# POWER.net
KiCad netlist of a schematic drawn in Altium Designer
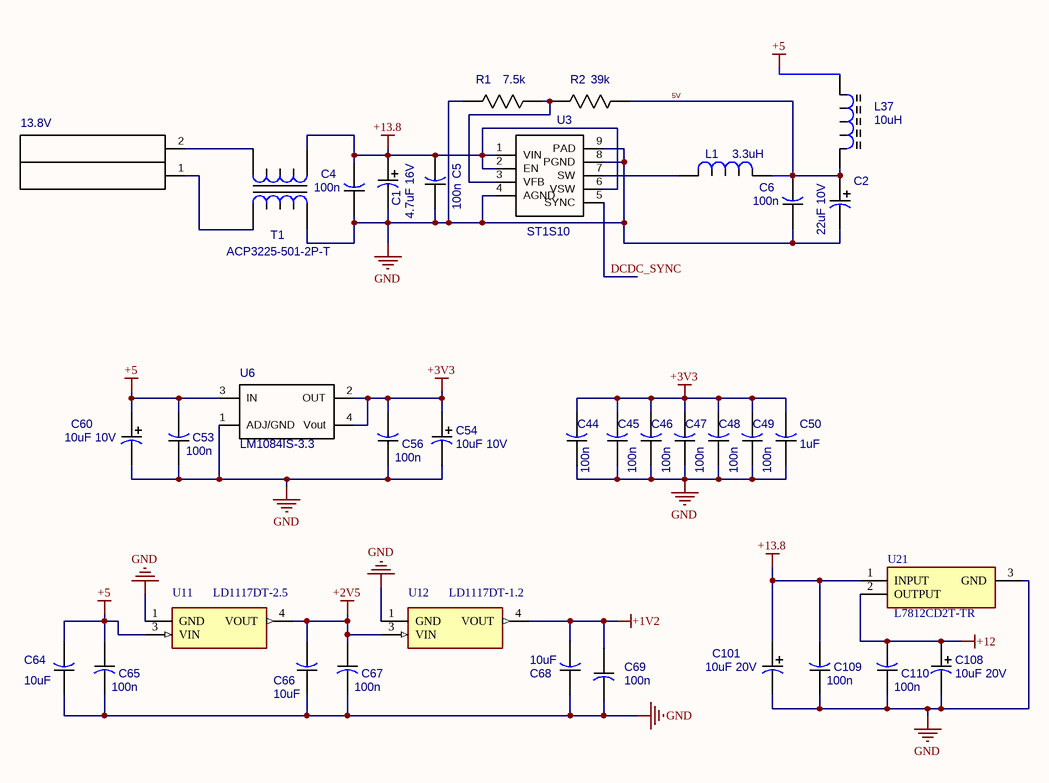
[diagram p0: POWER.SchDoc]

(export (version "E")
  (design (tool "Eeschema 10.0.6"))
  (components
    (comp (ref "13.8V") (value "JX2") (footprint "JX2") (libsource (lib "*") (part "JX2")))
    (comp (ref "C1")
      (value "4.7uF 16V")
      (footprint "CAPAE_6.6x6.6h5.4")
      (description "CAPAE_6.6x6.6h5.4")
      (libsource (lib "*") (part "CAPAE_6.6x6.6h5.4"))
    )
    (comp (ref "C2")
      (value "22uF 10V")
      (footprint "CAPAE_4.3x4.3h5.4")
      (description "CAPAE_4.3x4.3h5.4")
      (libsource (lib "*") (part "CAPAE_4.3x4.3h5.4"))
    )
    (comp (ref "C4")
      (value "100n")
      (footprint "CAP_0805")
      (description "CAP_0805")
      (libsource (lib "*") (part "CAP_0805"))
    )
    (comp (ref "C5")
      (value "100n")
      (footprint "CAP_0805")
      (description "CAP_0805")
      (libsource (lib "*") (part "CAP_0805"))
    )
    (comp (ref "C6")
      (value "100n")
      (footprint "CAP_0805")
      (description "CAP_0805")
      (libsource (lib "*") (part "CAP_0805"))
    )
    (comp (ref "C44")
      (value "100n")
      (footprint "CAP_0805")
      (description "CAP_0805")
      (libsource (lib "*") (part "CAP_0805"))
    )
    (comp (ref "C45")
      (value "100n")
      (footprint "CAP_0805")
      (description "CAP_0805")
      (libsource (lib "*") (part "CAP_0805"))
    )
    (comp (ref "C46")
      (value "100n")
      (footprint "CAP_0805")
      (description "CAP_0805")
      (libsource (lib "*") (part "CAP_0805"))
    )
    (comp (ref "C47")
      (value "100n")
      (footprint "CAP_0805")
      (description "CAP_0805")
      (libsource (lib "*") (part "CAP_0805"))
    )
    (comp (ref "C48")
      (value "100n")
      (footprint "CAP_0805")
      (description "CAP_0805")
      (libsource (lib "*") (part "CAP_0805"))
    )
    (comp (ref "C49")
      (value "100n")
      (footprint "CAP_0805")
      (description "CAP_0805")
      (libsource (lib "*") (part "CAP_0805"))
    )
    (comp (ref "C50")
      (value "1uF")
      (footprint "CAP_0805")
      (description "CAP_0805")
      (fields (field (name "Comment") "10uF"))
      (libsource (lib "*") (part "CAP_0805"))
    )
    (comp (ref "C53")
      (value "100n")
      (footprint "CAP_0805")
      (description "CAP_0805")
      (libsource (lib "*") (part "CAP_0805"))
    )
    (comp (ref "C54")
      (value "10uF 10V")
      (footprint "CAPAE_4.3x4.3h5.4")
      (description "CAPAE_4.3x4.3h5.4")
      (libsource (lib "*") (part "CAPAE_4.3x4.3h5.4"))
    )
    (comp (ref "C56")
      (value "100n")
      (footprint "CAP_0805")
      (description "CAP_0805")
      (libsource (lib "*") (part "CAP_0805"))
    )
    (comp (ref "C60")
      (value "10uF 10V")
      (footprint "CAPAE_4.3x4.3h5.4")
      (description "CAPAE_4.3x4.3h5.4")
      (libsource (lib "*") (part "CAPAE_4.3x4.3h5.4"))
    )
    (comp (ref "C64")
      (value "10uF")
      (footprint "CAP_0805")
      (description "CAP_0805")
      (libsource (lib "MOTHERBOARD") (part "CAP_0805"))
    )
    (comp (ref "C65")
      (value "100n")
      (footprint "CAP_0805")
      (description "CAP_0805")
      (libsource (lib "*") (part "CAP_0805"))
    )
    (comp (ref "C66")
      (value "10uF")
      (footprint "CAP_0805")
      (description "CAP_0805")
      (libsource (lib "MOTHERBOARD") (part "CAP_0805"))
    )
    (comp (ref "C67")
      (value "100n")
      (footprint "CAP_0805")
      (description "CAP_0805")
      (libsource (lib "*") (part "CAP_0805"))
    )
    (comp (ref "C68")
      (value "10uF")
      (footprint "CAP_0805")
      (description "CAP_0805")
      (libsource (lib "MOTHERBOARD") (part "CAP_0805"))
    )
    (comp (ref "C69")
      (value "100n")
      (footprint "CAP_0805")
      (description "CAP_0805")
      (libsource (lib "*") (part "CAP_0805"))
    )
    (comp (ref "C101")
      (value "10uF 20V")
      (footprint "CAPAE_4.3x4.3h5.4")
      (description "CAPAE_4.3x4.3h5.4")
      (libsource (lib "*") (part "CAPAE_4.3x4.3h5.4"))
    )
    (comp (ref "C108")
      (value "10uF 20V")
      (footprint "CAPAE_4.3x4.3h5.4")
      (description "CAPAE_4.3x4.3h5.4")
      (libsource (lib "*") (part "CAPAE_4.3x4.3h5.4"))
    )
    (comp (ref "C109")
      (value "100n")
      (footprint "CAP_0805")
      (description "CAP_0805")
      (libsource (lib "*") (part "CAP_0805"))
    )
    (comp (ref "C110")
      (value "100n")
      (footprint "CAP_0805")
      (description "CAP_0805")
      (libsource (lib "*") (part "CAP_0805"))
    )
    (comp (ref "L1")
      (value "3.3uH")
      (footprint "IND_1812")
      (description "IND_1812")
      (libsource (lib "*") (part "IND_1812"))
    )
    (comp (ref "L37")
      (value "10uH")
      (footprint "IND_FERRITE_CORE")
      (description "Inductor")
      (libsource (lib "MOTHERBOARD_1") (part "IND_FERRITE_CORE"))
    )
    (comp (ref "R1")
      (value "7.5k")
      (footprint "RES_0805")
      (description "RES_0805")
      (libsource (lib "*") (part "RES_0805"))
    )
    (comp (ref "R2")
      (value "39k")
      (footprint "RES_0805")
      (description "RES_0805")
      (libsource (lib "*") (part "RES_0805"))
    )
    (comp (ref "T1")
      (value "ACP3225-501-2P-T")
      (footprint "TRANSF_ICORE")
      (description "Transformer")
      (libsource (lib "*") (part "TRANSF_ICORE"))
    )
    (comp (ref "U3") (value "ST1S10") (footprint "ST1S10") (libsource (lib "*") (part "ST1S10")))
    (comp (ref "U6")
      (value "LM1084IS-3.3")
      (footprint "LM1085-3.3")
      (libsource (lib "*") (part "LM1085-3.3"))
    )
    (comp (ref "U11")
      (value "LD1117DT-2.5")
      (footprint "SamacSys:TO228P991X238-3N")
      (description "LD1117DT-2.5 DPAK")
      (fields
        (field (name "MANUFACTURER_PART_NUMBER") "LM1117DT-ADJ")
        (field (name "MOUSER PART NUMBER") "926-LM1117DT-ADJ")
      )
      (libsource (lib "*") (part "LM1117DT-ADJ"))
    )
    (comp (ref "U12")
      (value "LD1117DT-1.2")
      (footprint "SamacSys:TO228P991X238-3N")
      (description "LD1117DT-1.2 DPAK")
      (fields
        (field (name "MANUFACTURER_PART_NUMBER") "LM1117DT-ADJ")
        (field (name "MOUSER PART NUMBER") "926-LM1117DT-ADJ")
      )
      (libsource (lib "*") (part "LM1117DT-ADJ"))
    )
    (comp (ref "U21")
      (value "L7812CD2T-TR")
      (footprint "SamacSys:L7812CD2TTR")
      (description "Integrated Circuit")
      (fields (field (name "MOUSER PART NUMBER") "511-L7812CD2T-TR"))
      (libsource (lib "*") (part "L7812CD2T-TR"))
    )
  )
  (nets
    (net (code "1") (name "+1V2") (class "Default")
      (node (ref "C68") (pin "2") (pinfunction "2_2") (pintype "passive"))
      (node (ref "C69") (pin "1") (pinfunction "1_1") (pintype "passive"))
      (node (ref "U12") (pin "4") (pinfunction "VOUT_4") (pintype "output"))
    )
    (net (code "2") (name "+2V5") (class "Default")
      (node (ref "C66") (pin "2") (pinfunction "2_2") (pintype "passive"))
      (node (ref "C67") (pin "1") (pinfunction "1_1") (pintype "passive"))
      (node (ref "U11") (pin "4") (pinfunction "VOUT_4") (pintype "output"))
      (node (ref "U12") (pin "3") (pinfunction "VIN_3") (pintype "input"))
    )
    (net (code "3") (name "+3V3") (class "Default")
      (node (ref "C44") (pin "2") (pinfunction "2_2") (pintype "passive"))
      (node (ref "C45") (pin "2") (pinfunction "2_2") (pintype "passive"))
      (node (ref "C46") (pin "2") (pinfunction "2_2") (pintype "passive"))
      (node (ref "C47") (pin "2") (pinfunction "2_2") (pintype "passive"))
      (node (ref "C48") (pin "2") (pinfunction "2_2") (pintype "passive"))
      (node (ref "C49") (pin "2") (pinfunction "2_2") (pintype "passive"))
      (node (ref "C50") (pin "2") (pinfunction "2_2") (pintype "passive"))
      (node (ref "C54") (pin "1") (pinfunction "PLUS_1") (pintype "passive"))
      (node (ref "C56") (pin "2") (pinfunction "2_2") (pintype "passive"))
      (node (ref "U6") (pin "2") (pinfunction "OUT_2") (pintype "passive"))
      (node (ref "U6") (pin "4") (pinfunction "Vout_4") (pintype "passive"))
    )
    (net (code "4") (name "+5") (class "Default")
      (node (ref "C53") (pin "2") (pinfunction "2_2") (pintype "passive"))
      (node (ref "C60") (pin "1") (pinfunction "PLUS_1") (pintype "passive"))
      (node (ref "C64") (pin "2") (pinfunction "2_2") (pintype "passive"))
      (node (ref "C65") (pin "1") (pinfunction "1_1") (pintype "passive"))
      (node (ref "L37") (pin "1") (pinfunction "A_1") (pintype "passive"))
      (node (ref "U11") (pin "3") (pinfunction "VIN_3") (pintype "input"))
      (node (ref "U6") (pin "3") (pinfunction "IN_3") (pintype "passive"))
    )
    (net (code "5") (name "+12") (class "Default")
      (node (ref "C108") (pin "1") (pinfunction "PLUS_1") (pintype "passive"))
      (node (ref "C110") (pin "2") (pinfunction "2_2") (pintype "passive"))
      (node (ref "U21") (pin "2") (pinfunction "OUTPUT_2") (pintype "passive"))
    )
    (net (code "6") (name "+13.8") (class "Default")
      (node (ref "C1") (pin "1") (pinfunction "PLUS_1") (pintype "passive"))
      (node (ref "C101") (pin "1") (pinfunction "PLUS_1") (pintype "passive"))
      (node (ref "C109") (pin "2") (pinfunction "2_2") (pintype "passive"))
      (node (ref "C4") (pin "2") (pinfunction "2_2") (pintype "passive"))
      (node (ref "C5") (pin "2") (pinfunction "2_2") (pintype "passive"))
      (node (ref "T1") (pin "3") (pinfunction "P1_3") (pintype "passive"))
      (node (ref "U21") (pin "1") (pinfunction "INPUT_1") (pintype "passive"))
      (node (ref "U3") (pin "1") (pinfunction "VIN_1") (pintype "passive"))
      (node (ref "U3") (pin "2") (pinfunction "EN_2") (pintype "passive"))
      (node (ref "U3") (pin "6") (pinfunction "VSW_6") (pintype "passive"))
    )
    (net (code "7") (name "/5V") (class "Default")
      (node (ref "C2") (pin "1") (pinfunction "PLUS_1") (pintype "passive"))
      (node (ref "C6") (pin "2") (pinfunction "2_2") (pintype "passive"))
      (node (ref "L1") (pin "2") (pinfunction "2_2") (pintype "passive"))
      (node (ref "L37") (pin "2") (pinfunction "B_2") (pintype "passive"))
      (node (ref "R2") (pin "2") (pinfunction "2_2") (pintype "passive"))
    )
    (net (code "8") (name "/DCDC_SYNC") (class "Default")
      (node (ref "U3") (pin "5") (pinfunction "SYNC_5") (pintype "passive"))
    )
    (net (code "9") (name "GND") (class "Default")
      (node (ref "C1") (pin "2") (pinfunction "MINUS_2") (pintype "passive"))
      (node (ref "C101") (pin "2") (pinfunction "MINUS_2") (pintype "passive"))
      (node (ref "C108") (pin "2") (pinfunction "MINUS_2") (pintype "passive"))
      (node (ref "C109") (pin "1") (pinfunction "1_1") (pintype "passive"))
      (node (ref "C110") (pin "1") (pinfunction "1_1") (pintype "passive"))
      (node (ref "C2") (pin "2") (pinfunction "MINUS_2") (pintype "passive"))
      (node (ref "C4") (pin "1") (pinfunction "1_1") (pintype "passive"))
      (node (ref "C44") (pin "1") (pinfunction "1_1") (pintype "passive"))
      (node (ref "C45") (pin "1") (pinfunction "1_1") (pintype "passive"))
      (node (ref "C46") (pin "1") (pinfunction "1_1") (pintype "passive"))
      (node (ref "C47") (pin "1") (pinfunction "1_1") (pintype "passive"))
      (node (ref "C48") (pin "1") (pinfunction "1_1") (pintype "passive"))
      (node (ref "C49") (pin "1") (pinfunction "1_1") (pintype "passive"))
      (node (ref "C5") (pin "1") (pinfunction "1_1") (pintype "passive"))
      (node (ref "C50") (pin "1") (pinfunction "1_1") (pintype "passive"))
      (node (ref "C53") (pin "1") (pinfunction "1_1") (pintype "passive"))
      (node (ref "C54") (pin "2") (pinfunction "MINUS_2") (pintype "passive"))
      (node (ref "C56") (pin "1") (pinfunction "1_1") (pintype "passive"))
      (node (ref "C6") (pin "1") (pinfunction "1_1") (pintype "passive"))
      (node (ref "C60") (pin "2") (pinfunction "MINUS_2") (pintype "passive"))
      (node (ref "C64") (pin "1") (pinfunction "1_1") (pintype "passive"))
      (node (ref "C65") (pin "2") (pinfunction "2_2") (pintype "passive"))
      (node (ref "C66") (pin "1") (pinfunction "1_1") (pintype "passive"))
      (node (ref "C67") (pin "2") (pinfunction "2_2") (pintype "passive"))
      (node (ref "C68") (pin "1") (pinfunction "1_1") (pintype "passive"))
      (node (ref "C69") (pin "2") (pinfunction "2_2") (pintype "passive"))
      (node (ref "R1") (pin "1") (pinfunction "1_1") (pintype "passive"))
      (node (ref "T1") (pin "1") (pinfunction "S1_1") (pintype "passive"))
      (node (ref "U11") (pin "1") (pinfunction "GND_1") (pintype "passive"))
      (node (ref "U12") (pin "1") (pinfunction "GND_1") (pintype "passive"))
      (node (ref "U21") (pin "3") (pinfunction "GND_3") (pintype "passive"))
      (node (ref "U3") (pin "4") (pinfunction "AGND_4") (pintype "passive"))
      (node (ref "U3") (pin "8") (pinfunction "PGND_8") (pintype "passive"))
      (node (ref "U3") (pin "9") (pinfunction "PAD_9") (pintype "passive"))
      (node (ref "U6") (pin "1") (pinfunction "ADJ/GND_1") (pintype "passive"))
    )
    (net (code "10") (name "Net-(13.8V-1)") (class "Default")
      (node (ref "13.8V") (pin "2") (pinfunction "1_2") (pintype "passive"))
      (node (ref "T1") (pin "4") (pinfunction "P2_4") (pintype "passive"))
    )
    (net (code "11") (name "Net-(13.8V-2)") (class "Default")
      (node (ref "13.8V") (pin "1") (pinfunction "2_1") (pintype "passive"))
      (node (ref "T1") (pin "2") (pinfunction "S2_2") (pintype "passive"))
    )
    (net (code "12") (name "Net-(U3-SW)") (class "Default")
      (node (ref "L1") (pin "1") (pinfunction "1_1") (pintype "passive"))
      (node (ref "U3") (pin "7") (pinfunction "SW_7") (pintype "passive"))
    )
    (net (code "13") (name "Net-(U3-VFB)") (class "Default")
      (node (ref "R1") (pin "2") (pinfunction "2_2") (pintype "passive"))
      (node (ref "R2") (pin "1") (pinfunction "1_1") (pintype "passive"))
      (node (ref "U3") (pin "3") (pinfunction "VFB_3") (pintype "passive"))
    )
  )
)
